# rcv_board.net
KiCad netlist of a schematic drawn in EAGLE
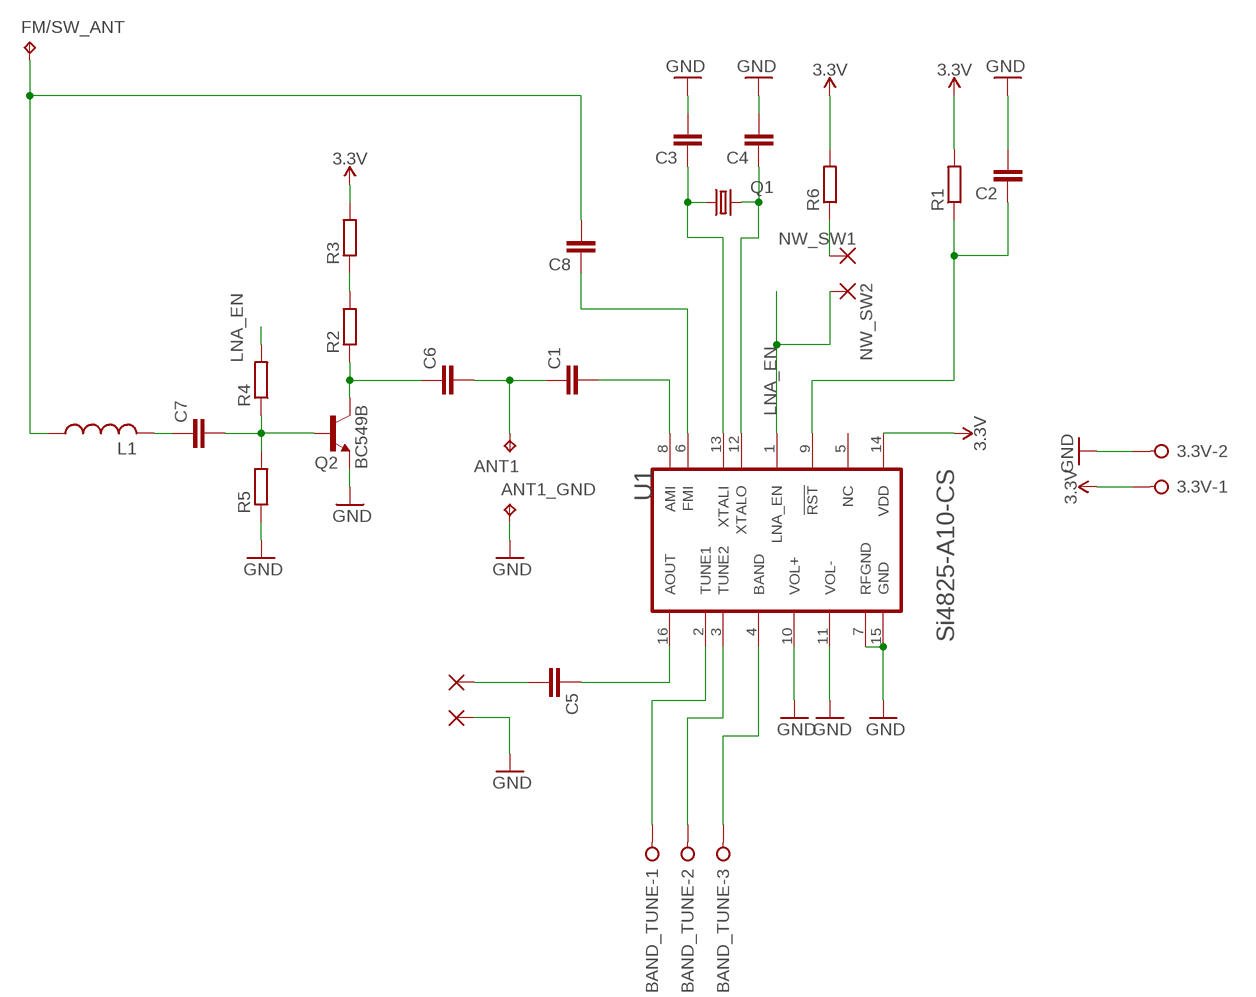
[diagram p0: schematic, sheet 1]

(export (version "E")
  (design (tool "Eeschema 10.0.6"))
  (components
    (comp (ref "3.3V")
      (value "W237-02P")
      (footprint "eagle-import:W237-132")
      (libsource (lib "eagle-import") (part "W237-02P"))
    )
    (comp (ref "ANT1")
      (value "TPPAD1-20Y")
      (footprint "eagle-import:P1-20Y")
      (libsource (lib "eagle-import") (part "TPPAD1-20Y"))
    )
    (comp (ref "ANT1_GND")
      (value "TPPAD1-20Y")
      (footprint "eagle-import:P1-20Y")
      (libsource (lib "eagle-import") (part "TPPAD1-20Y"))
    )
    (comp (ref "BAND_TUNE")
      (value "W237-03P")
      (footprint "eagle-import:W237-133")
      (libsource (lib "eagle-import") (part "W237-03P"))
    )
    (comp (ref "C1")
      (value "C-EUC0805")
      (footprint "eagle-import:C0805")
      (libsource (lib "eagle-import") (part "C-EUC0805"))
    )
    (comp (ref "C2")
      (value "C-EUC0805")
      (footprint "eagle-import:C0805")
      (libsource (lib "eagle-import") (part "C-EUC0805"))
    )
    (comp (ref "C3")
      (value "C-EUC0805")
      (footprint "eagle-import:C0805")
      (libsource (lib "eagle-import") (part "C-EUC0805"))
    )
    (comp (ref "C4")
      (value "C-EUC0805")
      (footprint "eagle-import:C0805")
      (libsource (lib "eagle-import") (part "C-EUC0805"))
    )
    (comp (ref "C5")
      (value "C-EU050-035X075")
      (footprint "eagle-import:C050-035X075")
      (libsource (lib "eagle-import") (part "C-EU050-035X075"))
    )
    (comp (ref "C6")
      (value "C-EUC0805")
      (footprint "eagle-import:C0805")
      (libsource (lib "eagle-import") (part "C-EUC0805"))
    )
    (comp (ref "C7")
      (value "C-EUC0805")
      (footprint "eagle-import:C0805")
      (libsource (lib "eagle-import") (part "C-EUC0805"))
    )
    (comp (ref "C8")
      (value "C-EUC0805")
      (footprint "eagle-import:C0805")
      (libsource (lib "eagle-import") (part "C-EUC0805"))
    )
    (comp (ref "FM/SW_ANT")
      (value "TPPAD1-17")
      (footprint "eagle-import:P1-17")
      (libsource (lib "eagle-import") (part "TPPAD1-17"))
    )
    (comp (ref "L1")
      (value "L-US0204V")
      (footprint "eagle-import:0204V")
      (libsource (lib "eagle-import") (part "L-US0204V"))
    )
    (comp (ref "OGND")
      (value "NW_SW1")
      (footprint "eagle-import:2,54_1,0")
      (libsource (lib "eagle-import") (part "2,54/1,0"))
    )
    (comp (ref "OUT")
      (value "NW_SW1")
      (footprint "eagle-import:2,54_1,0")
      (libsource (lib "eagle-import") (part "2,54/1,0"))
    )
    (comp (ref "PAD1")
      (value "NW_SW1")
      (footprint "eagle-import:2,54_1,0")
      (libsource (lib "eagle-import") (part "2,54/1,0"))
    )
    (comp (ref "PAD2")
      (value "NW_SW2")
      (footprint "eagle-import:2,54_1,0")
      (libsource (lib "eagle-import") (part "2,54/1,0"))
    )
    (comp (ref "Q1")
      (value "KX-327-NHF")
      (footprint "eagle-import:3.2X1.5")
      (libsource (lib "eagle-import") (part "KX-327-NHF"))
    )
    (comp (ref "Q2")
      (value "BC549B")
      (footprint "eagle-import:TO92-EBC")
      (libsource (lib "eagle-import") (part "BC549B"))
    )
    (comp (ref "R1")
      (value "R-EU_R0805")
      (footprint "eagle-import:R0805")
      (libsource (lib "eagle-import") (part "R-EU_R0805"))
    )
    (comp (ref "R2")
      (value "R-EU_R0805")
      (footprint "eagle-import:R0805")
      (libsource (lib "eagle-import") (part "R-EU_R0805"))
    )
    (comp (ref "R3")
      (value "R-EU_R0805")
      (footprint "eagle-import:R0805")
      (libsource (lib "eagle-import") (part "R-EU_R0805"))
    )
    (comp (ref "R4")
      (value "R-EU_R0805")
      (footprint "eagle-import:R0805")
      (libsource (lib "eagle-import") (part "R-EU_R0805"))
    )
    (comp (ref "R5")
      (value "R-EU_R0805")
      (footprint "eagle-import:R0805")
      (libsource (lib "eagle-import") (part "R-EU_R0805"))
    )
    (comp (ref "R6")
      (value "R-EU_R0805")
      (footprint "eagle-import:R0805")
      (libsource (lib "eagle-import") (part "R-EU_R0805"))
    )
    (comp (ref "U1")
      (value "SILICON_LABS_SI4825-A10-CSSILICON_LABS_SI4825-A10-CS_0_2")
      (footprint "eagle-import:SILICON_LABS_SI4825-A10-CS_2")
      (fields (field (name "MF") "Silicon Labs") (field (name "MPN") "Si4825-A10-CS"))
      (libsource (lib "eagle-import") (part "SILICON_LABS_SI4825-A10-CSSILICON_LABS_SI4825-A10-CS_0_2"))
    )
  )
  (nets
    (net (code "1") (name "/LNA_EN") (class "Default")
      (node (ref "PAD2") (pin "1") (pinfunction "P_1") (pintype "passive"))
      (node (ref "R4") (pin "2") (pinfunction "2_2") (pintype "passive"))
      (node (ref "U1") (pin "1") (pinfunction "LNA_EN_1") (pintype "input"))
    )
    (net (code "2") (name "3.3V") (class "Default")
      (node (ref "3.3V") (pin "1") (pinfunction "KL_1") (pintype "passive"))
      (node (ref "R1") (pin "2") (pinfunction "2_2") (pintype "passive"))
      (node (ref "R3") (pin "2") (pinfunction "2_2") (pintype "passive"))
      (node (ref "R6") (pin "2") (pinfunction "2_2") (pintype "passive"))
      (node (ref "U1") (pin "14") (pinfunction "VDD_14") (pintype "power_in"))
    )
    (net (code "3") (name "GND") (class "Default")
      (node (ref "3.3V") (pin "2") (pinfunction "KL_2") (pintype "passive"))
      (node (ref "ANT1_GND") (pin "TP") (pinfunction "TP_TP") (pintype "input"))
      (node (ref "C2") (pin "2") (pinfunction "2_2") (pintype "passive"))
      (node (ref "C3") (pin "2") (pinfunction "2_2") (pintype "passive"))
      (node (ref "C4") (pin "2") (pinfunction "2_2") (pintype "passive"))
      (node (ref "OGND") (pin "1") (pinfunction "P_1") (pintype "passive"))
      (node (ref "Q2") (pin "E") (pinfunction "E_E") (pintype "passive"))
      (node (ref "R5") (pin "1") (pinfunction "1_1") (pintype "passive"))
      (node (ref "U1") (pin "10") (pinfunction "VOL+_10") (pintype "input"))
      (node (ref "U1") (pin "11") (pinfunction "VOL-_11") (pintype "input"))
      (node (ref "U1") (pin "15") (pinfunction "GND_15") (pintype "power_in"))
      (node (ref "U1") (pin "7") (pinfunction "RFGND_7") (pintype "power_in"))
    )
    (net (code "4") (name "Net-(ANT1-PadTP)") (class "Default")
      (node (ref "ANT1") (pin "TP") (pinfunction "TP_TP") (pintype "input"))
      (node (ref "C1") (pin "1") (pinfunction "1_1") (pintype "passive"))
      (node (ref "C6") (pin "2") (pinfunction "2_2") (pintype "passive"))
    )
    (net (code "5") (name "Net-(BAND_TUNEA-KL)") (class "Default")
      (node (ref "BAND_TUNE") (pin "1") (pinfunction "KL_1") (pintype "passive"))
      (node (ref "U1") (pin "2") (pinfunction "TUNE1_2") (pintype "input"))
    )
    (net (code "6") (name "Net-(BAND_TUNEB-KL)") (class "Default")
      (node (ref "BAND_TUNE") (pin "2") (pinfunction "KL_2") (pintype "passive"))
      (node (ref "U1") (pin "3") (pinfunction "TUNE2_3") (pintype "input"))
    )
    (net (code "7") (name "Net-(BAND_TUNEC-KL)") (class "Default")
      (node (ref "BAND_TUNE") (pin "3") (pinfunction "KL_3") (pintype "passive"))
      (node (ref "U1") (pin "4") (pinfunction "BAND_4") (pintype "input"))
    )
    (net (code "8") (name "Net-(C6-Pad1)") (class "Default")
      (node (ref "C6") (pin "1") (pinfunction "1_1") (pintype "passive"))
      (node (ref "Q2") (pin "C") (pinfunction "C_C") (pintype "passive"))
      (node (ref "R2") (pin "1") (pinfunction "1_1") (pintype "passive"))
    )
    (net (code "9") (name "Net-(C7-Pad1)") (class "Default")
      (node (ref "C7") (pin "1") (pinfunction "1_1") (pintype "passive"))
      (node (ref "L1") (pin "2") (pinfunction "2_2") (pintype "passive"))
    )
    (net (code "10") (name "Net-(C7-Pad2)") (class "Default")
      (node (ref "C7") (pin "2") (pinfunction "2_2") (pintype "passive"))
      (node (ref "Q2") (pin "B") (pinfunction "B_B") (pintype "passive"))
      (node (ref "R4") (pin "1") (pinfunction "1_1") (pintype "passive"))
      (node (ref "R5") (pin "2") (pinfunction "2_2") (pintype "passive"))
    )
    (net (code "11") (name "Net-(C8-Pad2)") (class "Default")
      (node (ref "C8") (pin "2") (pinfunction "2_2") (pintype "passive"))
      (node (ref "FM/SW_ANT") (pin "TP") (pinfunction "TP_TP") (pintype "input"))
      (node (ref "L1") (pin "1") (pinfunction "1_1") (pintype "passive"))
    )
    (net (code "12") (name "Net-(OUT-P)") (class "Default")
      (node (ref "C5") (pin "2") (pinfunction "2_2") (pintype "passive"))
      (node (ref "OUT") (pin "1") (pinfunction "P_1") (pintype "passive"))
    )
    (net (code "13") (name "Net-(PAD1-P)") (class "Default")
      (node (ref "PAD1") (pin "1") (pinfunction "P_1") (pintype "passive"))
      (node (ref "R6") (pin "1") (pinfunction "1_1") (pintype "passive"))
    )
    (net (code "14") (name "Net-(R2-Pad2)") (class "Default")
      (node (ref "R2") (pin "2") (pinfunction "2_2") (pintype "passive"))
      (node (ref "R3") (pin "1") (pinfunction "1_1") (pintype "passive"))
    )
    (net (code "15") (name "Net-(U1-AMI)") (class "Default")
      (node (ref "C1") (pin "2") (pinfunction "2_2") (pintype "passive"))
      (node (ref "U1") (pin "8") (pinfunction "AMI_8") (pintype "input"))
    )
    (net (code "16") (name "Net-(U1-AOUT)") (class "Default")
      (node (ref "C5") (pin "1") (pinfunction "1_1") (pintype "passive"))
      (node (ref "U1") (pin "16") (pinfunction "AOUT_16") (pintype "output"))
    )
    (net (code "17") (name "Net-(U1-FMI)") (class "Default")
      (node (ref "C8") (pin "1") (pinfunction "1_1") (pintype "passive"))
      (node (ref "U1") (pin "6") (pinfunction "FMI_6") (pintype "input"))
    )
    (net (code "18") (name "Net-(U1-XTALI)") (class "Default")
      (node (ref "C3") (pin "1") (pinfunction "1_1") (pintype "passive"))
      (node (ref "Q1") (pin "1") (pinfunction "1_1") (pintype "passive"))
      (node (ref "U1") (pin "13") (pinfunction "XTALI_13") (pintype "input"))
    )
    (net (code "19") (name "Net-(U1-XTALO)") (class "Default")
      (node (ref "C4") (pin "1") (pinfunction "1_1") (pintype "passive"))
      (node (ref "Q1") (pin "2") (pinfunction "2_2") (pintype "passive"))
      (node (ref "U1") (pin "12") (pinfunction "XTALO_12") (pintype "passive"))
    )
    (net (code "20") (name "Net-(U1-~{RST})") (class "Default")
      (node (ref "C2") (pin "1") (pinfunction "1_1") (pintype "passive"))
      (node (ref "R1") (pin "1") (pinfunction "1_1") (pintype "passive"))
      (node (ref "U1") (pin "9") (pinfunction "~{RST}_9") (pintype "input"))
    )
    (net (code "21") (name "unconnected-(U1-NC-Pad5)") (class "Default")
      (node (ref "U1") (pin "5") (pinfunction "NC_5") (pintype "passive"))
    )
  )
)
